# Steering_Wheel_ECU.net
KiCad netlist of a schematic drawn in Altium Designer
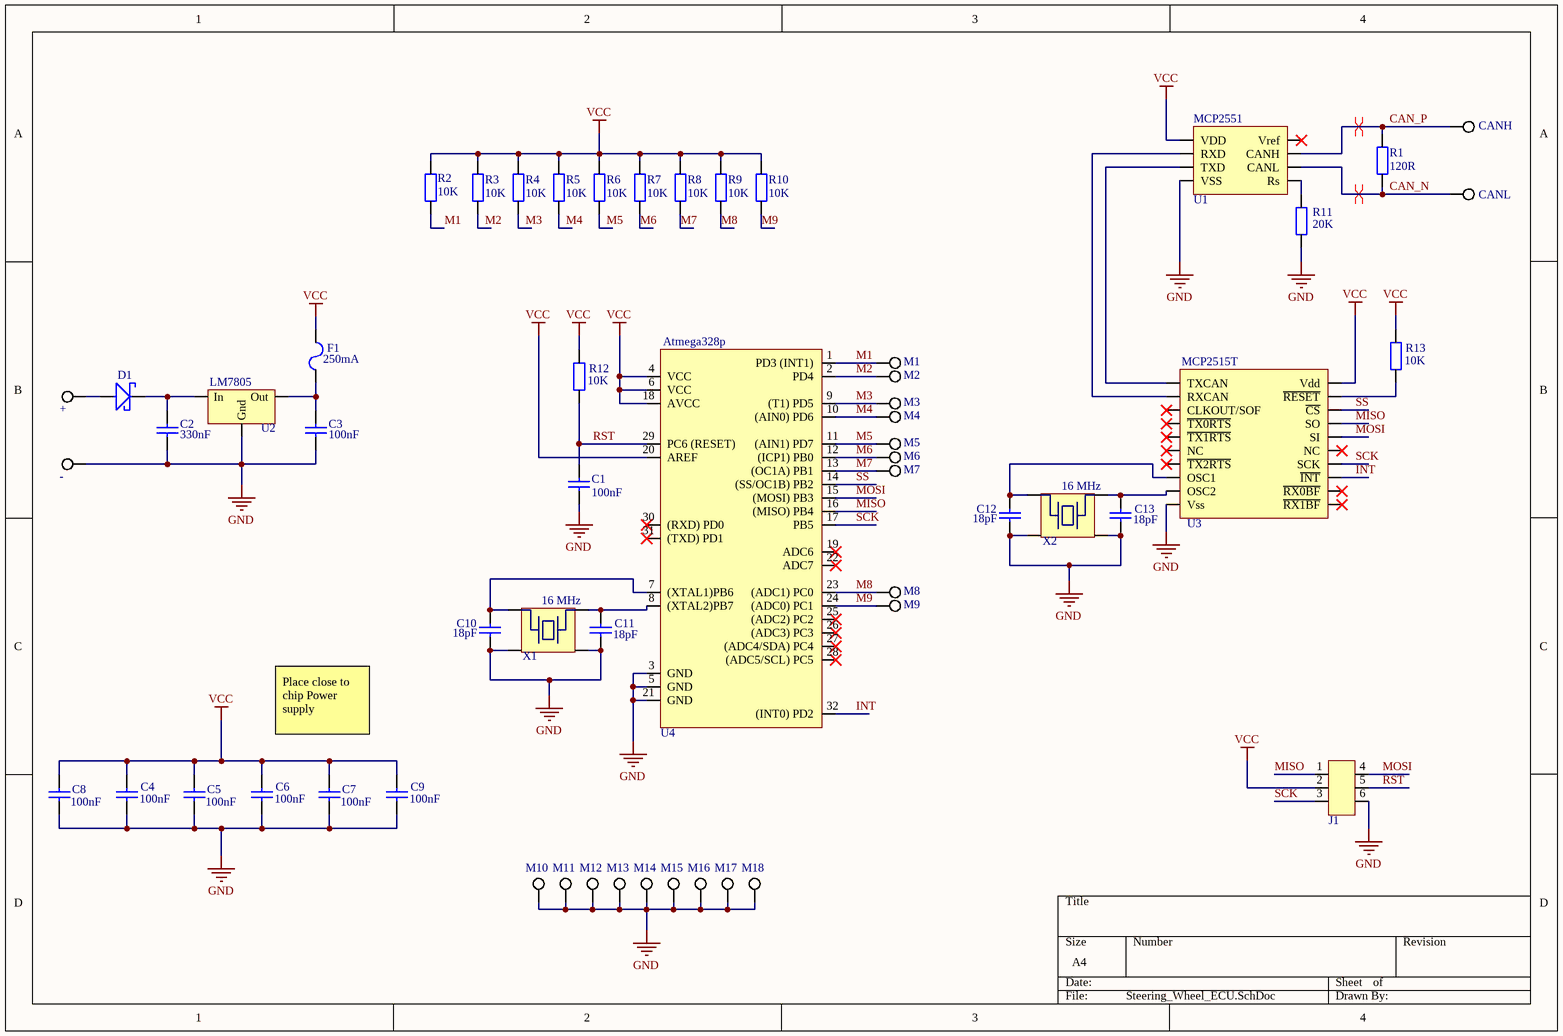
[diagram p0: Steering_Wheel_ECU.SchDoc]

(export (version "E")
  (design (tool "Eeschema 10.0.6"))
  (components
    (comp (ref "+")
      (value "0.7mm")
      (footprint "HOLE_0.7MM")
      (fields (field (name "PART NUMBER") "Hole_0.7mm"))
      (libsource (lib "Database_Libs1") (part "Hole"))
    )
    (comp (ref "-")
      (value "0.7mm")
      (footprint "HOLE_0.7MM")
      (fields (field (name "PART NUMBER") "Hole_0.7mm"))
      (libsource (lib "Database_Libs1") (part "Hole"))
    )
    (comp (ref "C1")
      (value "100nF")
      (footprint "CAPC160X80X87L35N")
      (fields
        (field (name "PART NUMBER") "C_0603_100nF_50V")
        (field (name "MANUFACTURER PART NUMBER") "CC0603MRY5V9BB104")
      )
      (libsource (lib "Database_Libs1") (part "Capacitor_NP"))
    )
    (comp (ref "C2")
      (value "330nF")
      (footprint "CAPC320X160X90L50N")
      (fields
        (field (name "PART NUMBER") "C_1206_330nF_50V")
        (field (name "MANUFACTURER PART NUMBER") "1206B334K500CT")
      )
      (libsource (lib "Database_Libs1") (part "Capacitor_NP"))
    )
    (comp (ref "C3")
      (value "100nF")
      (footprint "CAPC160X80X87L35N")
      (fields
        (field (name "PART NUMBER") "C_0603_100nF_50V")
        (field (name "MANUFACTURER PART NUMBER") "CC0603MRY5V9BB104")
      )
      (libsource (lib "Database_Libs1") (part "Capacitor_NP"))
    )
    (comp (ref "C4")
      (value "100nF")
      (footprint "CAPC160X80X87L35N")
      (fields
        (field (name "PART NUMBER") "C_0603_100nF_50V")
        (field (name "MANUFACTURER PART NUMBER") "CC0603MRY5V9BB104")
      )
      (libsource (lib "Database_Libs1") (part "Capacitor_NP"))
    )
    (comp (ref "C5")
      (value "100nF")
      (footprint "CAPC160X80X87L35N")
      (fields
        (field (name "PART NUMBER") "C_0603_100nF_50V")
        (field (name "MANUFACTURER PART NUMBER") "CC0603MRY5V9BB104")
      )
      (libsource (lib "Database_Libs1") (part "Capacitor_NP"))
    )
    (comp (ref "C6")
      (value "100nF")
      (footprint "CAPC160X80X87L35N")
      (fields
        (field (name "PART NUMBER") "C_0603_100nF_50V")
        (field (name "MANUFACTURER PART NUMBER") "CC0603MRY5V9BB104")
      )
      (libsource (lib "Database_Libs1") (part "Capacitor_NP"))
    )
    (comp (ref "C7")
      (value "100nF")
      (footprint "CAPC160X80X87L35N")
      (fields
        (field (name "PART NUMBER") "C_0603_100nF_50V")
        (field (name "MANUFACTURER PART NUMBER") "CC0603MRY5V9BB104")
      )
      (libsource (lib "Database_Libs1") (part "Capacitor_NP"))
    )
    (comp (ref "C8")
      (value "100nF")
      (footprint "CAPC160X80X87L35N")
      (fields
        (field (name "PART NUMBER") "C_0603_100nF_50V")
        (field (name "MANUFACTURER PART NUMBER") "CC0603MRY5V9BB104")
      )
      (libsource (lib "Database_Libs1") (part "Capacitor_NP"))
    )
    (comp (ref "C9")
      (value "100nF")
      (footprint "CAPC160X80X87L35N")
      (fields
        (field (name "PART NUMBER") "C_0603_100nF_50V")
        (field (name "MANUFACTURER PART NUMBER") "CC0603MRY5V9BB104")
      )
      (libsource (lib "Database_Libs1") (part "Capacitor_NP"))
    )
    (comp (ref "C10")
      (value "18pF")
      (footprint "CAPC152X76X91L25N")
      (fields
        (field (name "PART NUMBER") "C_0603_18pF_50V")
        (field (name "MANUFACTURER PART NUMBER") "06035U180GAT2A")
      )
      (libsource (lib "Database_Libs1") (part "Capacitor_NP"))
    )
    (comp (ref "C11")
      (value "18pF")
      (footprint "CAPC152X76X91L25N")
      (fields
        (field (name "PART NUMBER") "C_0603_18pF_50V")
        (field (name "MANUFACTURER PART NUMBER") "06035U180GAT2A")
      )
      (libsource (lib "Database_Libs1") (part "Capacitor_NP"))
    )
    (comp (ref "C12")
      (value "18pF")
      (footprint "CAPC152X76X91L25N")
      (fields
        (field (name "PART NUMBER") "C_0603_18pF_50V")
        (field (name "MANUFACTURER PART NUMBER") "06035U180GAT2A")
      )
      (libsource (lib "Database_Libs1") (part "Capacitor_NP"))
    )
    (comp (ref "C13")
      (value "18pF")
      (footprint "CAPC152X76X91L25N")
      (fields
        (field (name "PART NUMBER") "C_0603_18pF_50V")
        (field (name "MANUFACTURER PART NUMBER") "06035U180GAT2A")
      )
      (libsource (lib "Database_Libs1") (part "Capacitor_NP"))
    )
    (comp (ref "CANH")
      (value "0.7mm")
      (footprint "HOLE_0.7MM")
      (fields (field (name "PART NUMBER") "Hole_0.7mm"))
      (libsource (lib "Database_Libs1") (part "Hole"))
    )
    (comp (ref "CANL")
      (value "0.7mm")
      (footprint "HOLE_0.7MM")
      (fields (field (name "PART NUMBER") "Hole_0.7mm"))
      (libsource (lib "Database_Libs1") (part "Hole"))
    )
    (comp (ref "D1")
      (value "MBR0540")
      (footprint "SOD375X160X128L31X60N")
      (libsource (lib "Database_Libs1") (part "S_Diode"))
    )
    (comp (ref "F1")
      (value "250mA")
      (footprint "FUSC325X165X75L42N")
      (fields (field (name "PART NUMBER") "F_250mA") (field (name "MANUFACTURER PART NUMBER") "0ZCJ0025FF2E"))
      (libsource (lib "Database_Libs1") (part "Fuse"))
    )
    (comp (ref "J1")
      (value "Header_2x3")
      (footprint "HDRV6W64P254_3X2_762X508H1100N")
      (fields (field (name "MANUFACTURER PART NUMBER") "M20-9970345"))
      (libsource (lib "Database_Libs1") (part "Header_2x3"))
    )
    (comp (ref "M1")
      (value "0.7mm")
      (footprint "HOLE_0.7MM")
      (fields (field (name "PART NUMBER") "Hole_0.7mm"))
      (libsource (lib "Database_Libs1") (part "Hole"))
    )
    (comp (ref "M2")
      (value "0.7mm")
      (footprint "HOLE_0.7MM")
      (fields (field (name "PART NUMBER") "Hole_0.7mm"))
      (libsource (lib "Database_Libs1") (part "Hole"))
    )
    (comp (ref "M3")
      (value "0.7mm")
      (footprint "HOLE_0.7MM")
      (fields (field (name "PART NUMBER") "Hole_0.7mm"))
      (libsource (lib "Database_Libs1") (part "Hole"))
    )
    (comp (ref "M4")
      (value "0.7mm")
      (footprint "HOLE_0.7MM")
      (fields (field (name "PART NUMBER") "Hole_0.7mm"))
      (libsource (lib "Database_Libs1") (part "Hole"))
    )
    (comp (ref "M5")
      (value "0.7mm")
      (footprint "HOLE_0.7MM")
      (fields (field (name "PART NUMBER") "Hole_0.7mm"))
      (libsource (lib "Database_Libs1") (part "Hole"))
    )
    (comp (ref "M6")
      (value "0.7mm")
      (footprint "HOLE_0.7MM")
      (fields (field (name "PART NUMBER") "Hole_0.7mm"))
      (libsource (lib "Database_Libs1") (part "Hole"))
    )
    (comp (ref "M7")
      (value "0.7mm")
      (footprint "HOLE_0.7MM")
      (fields (field (name "PART NUMBER") "Hole_0.7mm"))
      (libsource (lib "Database_Libs1") (part "Hole"))
    )
    (comp (ref "M8")
      (value "0.7mm")
      (footprint "HOLE_0.7MM")
      (fields (field (name "PART NUMBER") "Hole_0.7mm"))
      (libsource (lib "Database_Libs1") (part "Hole"))
    )
    (comp (ref "M9")
      (value "0.7mm")
      (footprint "HOLE_0.7MM")
      (fields (field (name "PART NUMBER") "Hole_0.7mm"))
      (libsource (lib "Database_Libs1") (part "Hole"))
    )
    (comp (ref "M10")
      (value "0.7mm")
      (footprint "HOLE_0.7MM")
      (fields (field (name "PART NUMBER") "Hole_0.7mm"))
      (libsource (lib "Database_Libs1") (part "Hole"))
    )
    (comp (ref "M11")
      (value "0.7mm")
      (footprint "HOLE_0.7MM")
      (fields (field (name "PART NUMBER") "Hole_0.7mm"))
      (libsource (lib "Database_Libs1") (part "Hole"))
    )
    (comp (ref "M12")
      (value "0.7mm")
      (footprint "HOLE_0.7MM")
      (fields (field (name "PART NUMBER") "Hole_0.7mm"))
      (libsource (lib "Database_Libs1") (part "Hole"))
    )
    (comp (ref "M13")
      (value "0.7mm")
      (footprint "HOLE_0.7MM")
      (fields (field (name "PART NUMBER") "Hole_0.7mm"))
      (libsource (lib "Database_Libs1") (part "Hole"))
    )
    (comp (ref "M14")
      (value "0.7mm")
      (footprint "HOLE_0.7MM")
      (fields (field (name "PART NUMBER") "Hole_0.7mm"))
      (libsource (lib "Database_Libs1") (part "Hole"))
    )
    (comp (ref "M15")
      (value "0.7mm")
      (footprint "HOLE_0.7MM")
      (fields (field (name "PART NUMBER") "Hole_0.7mm"))
      (libsource (lib "Database_Libs1") (part "Hole"))
    )
    (comp (ref "M16")
      (value "0.7mm")
      (footprint "HOLE_0.7MM")
      (fields (field (name "PART NUMBER") "Hole_0.7mm"))
      (libsource (lib "Database_Libs1") (part "Hole"))
    )
    (comp (ref "M17")
      (value "0.7mm")
      (footprint "HOLE_0.7MM")
      (fields (field (name "PART NUMBER") "Hole_0.7mm"))
      (libsource (lib "Database_Libs1") (part "Hole"))
    )
    (comp (ref "M18")
      (value "0.7mm")
      (footprint "HOLE_0.7MM")
      (fields (field (name "PART NUMBER") "Hole_0.7mm"))
      (libsource (lib "Database_Libs1") (part "Hole"))
    )
    (comp (ref "R1")
      (value "120R")
      (footprint "RESC160X80X50L30N")
      (fields
        (field (name "PART NUMBER") "R_0805_120R_0W5")
        (field (name "MANUFACTURER PART NUMBER") "SG73G2ATTD1200D")
      )
      (libsource (lib "Database_Libs1") (part "Resistor"))
    )
    (comp (ref "R2")
      (value "10K")
      (footprint "RESC160X80X50L30N")
      (fields
        (field (name "PART NUMBER") "R_0603_10K_0W062_P")
        (field (name "MANUFACTURER PART NUMBER") "APC0603B10K0N")
      )
      (libsource (lib "Database_Libs1") (part "Resistor"))
    )
    (comp (ref "R3")
      (value "10K")
      (footprint "RESC160X80X50L30N")
      (fields
        (field (name "PART NUMBER") "R_0603_10K_0W062_P")
        (field (name "MANUFACTURER PART NUMBER") "APC0603B10K0N")
      )
      (libsource (lib "Database_Libs1") (part "Resistor"))
    )
    (comp (ref "R4")
      (value "10K")
      (footprint "RESC160X80X50L30N")
      (fields
        (field (name "PART NUMBER") "R_0603_10K_0W062_P")
        (field (name "MANUFACTURER PART NUMBER") "APC0603B10K0N")
      )
      (libsource (lib "Database_Libs1") (part "Resistor"))
    )
    (comp (ref "R5")
      (value "10K")
      (footprint "RESC160X80X50L30N")
      (fields
        (field (name "PART NUMBER") "R_0603_10K_0W062_P")
        (field (name "MANUFACTURER PART NUMBER") "APC0603B10K0N")
      )
      (libsource (lib "Database_Libs1") (part "Resistor"))
    )
    (comp (ref "R6")
      (value "10K")
      (footprint "RESC160X80X50L30N")
      (fields
        (field (name "PART NUMBER") "R_0603_10K_0W062_P")
        (field (name "MANUFACTURER PART NUMBER") "APC0603B10K0N")
      )
      (libsource (lib "Database_Libs1") (part "Resistor"))
    )
    (comp (ref "R7")
      (value "10K")
      (footprint "RESC160X80X50L30N")
      (fields
        (field (name "PART NUMBER") "R_0603_10K_0W062_P")
        (field (name "MANUFACTURER PART NUMBER") "APC0603B10K0N")
      )
      (libsource (lib "Database_Libs1") (part "Resistor"))
    )
    (comp (ref "R8")
      (value "10K")
      (footprint "RESC160X80X50L30N")
      (fields
        (field (name "PART NUMBER") "R_0603_10K_0W062_P")
        (field (name "MANUFACTURER PART NUMBER") "APC0603B10K0N")
      )
      (libsource (lib "Database_Libs1") (part "Resistor"))
    )
    (comp (ref "R9")
      (value "10K")
      (footprint "RESC160X80X50L30N")
      (fields
        (field (name "PART NUMBER") "R_0603_10K_0W062_P")
        (field (name "MANUFACTURER PART NUMBER") "APC0603B10K0N")
      )
      (libsource (lib "Database_Libs1") (part "Resistor"))
    )
    (comp (ref "R10")
      (value "10K")
      (footprint "RESC160X80X50L30N")
      (fields
        (field (name "PART NUMBER") "R_0603_10K_0W062_P")
        (field (name "MANUFACTURER PART NUMBER") "APC0603B10K0N")
      )
      (libsource (lib "Database_Libs1") (part "Resistor"))
    )
    (comp (ref "R11")
      (value "20K")
      (footprint "RESC160X80X50L30N")
      (fields
        (field (name "PART NUMBER") "R_0603_20K_0W1")
        (field (name "MANUFACTURER PART NUMBER") "RT0603DRE0720KL")
      )
      (libsource (lib "Database_Libs1") (part "Resistor"))
    )
    (comp (ref "R12")
      (value "10K")
      (footprint "RESC160X80X50L30N")
      (fields
        (field (name "PART NUMBER") "R_0603_10K_0W062_P")
        (field (name "MANUFACTURER PART NUMBER") "APC0603B10K0N")
      )
      (libsource (lib "Database_Libs1") (part "Resistor"))
    )
    (comp (ref "R13")
      (value "10K")
      (footprint "RESC160X80X50L30N")
      (fields
        (field (name "PART NUMBER") "R_0603_10K_0W062_P")
        (field (name "MANUFACTURER PART NUMBER") "APC0603B10K0N")
      )
      (libsource (lib "Database_Libs1") (part "Resistor"))
    )
    (comp (ref "U1")
      (value "MCP2551")
      (footprint "SOIC8P127_490X600X175L83X24N")
      (fields (field (name "MANUFACTURER PART NUMBER") "MCP2551-I/SN"))
      (libsource (lib "Database_Libs1") (part "MCP2551"))
    )
    (comp (ref "U2")
      (value "LM7805")
      (footprint "SOT223-4P230_700X180L80X75N")
      (fields (field (name "PART NUMBER") "U_5V") (field (name "MANUFACTURER PART NUMBER") "UA78M05CDCYR"))
      (libsource (lib "Database_Libs1") (part "V_REG"))
    )
    (comp (ref "U3")
      (value "MCP2515T")
      (footprint "SOP20P65_650X640X120L60X24N")
      (fields
        (field (name "PART NUMBER") "MCP2515")
        (field (name "MANUFACTURER PART NUMBER") "MCP2515T-I/ST")
      )
      (libsource (lib "Database_Libs1") (part "MCP2515"))
    )
    (comp (ref "U4")
      (value "Atmega328p")
      (footprint "QFP32P80_900X900X120L60X37N")
      (fields (field (name "MANUFACTURER PART NUMBER") "ATMEGA328P-AUR"))
      (libsource (lib "Database_Libs1") (part "Atmega328p"))
    )
    (comp (ref "X1")
      (value "16 MHz")
      (footprint "OSCCC320X250X60L90X110N")
      (fields
        (field (name "PART NUMBER") "X_16MHZ_9pF")
        (field (name "MANUFACTURER PART NUMBER") "TSX-3225 16.0000MF09Z-AC3")
      )
      (libsource (lib "Database_Libs1") (part "OSC_4pin"))
    )
    (comp (ref "X2")
      (value "16 MHz")
      (footprint "OSCCC320X250X60L90X110N")
      (fields
        (field (name "PART NUMBER") "X_16MHZ_9pF")
        (field (name "MANUFACTURER PART NUMBER") "TSX-3225 16.0000MF09Z-AC3")
      )
      (libsource (lib "Database_Libs1") (part "OSC_4pin"))
    )
  )
  (nets
    (net (code "1") (name "/CAN_N") (class "Default")
      (node (ref "CANL") (pin "1") (pinfunction "11_1") (pintype "passive"))
      (node (ref "R1") (pin "2") (pinfunction "2_2") (pintype "passive"))
      (node (ref "U1") (pin "6") (pinfunction "CANL_6") (pintype "passive"))
    )
    (net (code "2") (name "/CAN_P") (class "Default")
      (node (ref "CANH") (pin "1") (pinfunction "11_1") (pintype "passive"))
      (node (ref "R1") (pin "1") (pinfunction "1_1") (pintype "passive"))
      (node (ref "U1") (pin "7") (pinfunction "CANH_7") (pintype "passive"))
    )
    (net (code "3") (name "/INT") (class "Default")
      (node (ref "U3") (pin "13") (pinfunction "~{INT}_13") (pintype "passive"))
      (node (ref "U4") (pin "32") (pinfunction "(INT0)_PD2_32") (pintype "passive"))
    )
    (net (code "4") (name "/M1") (class "Default")
      (node (ref "M1") (pin "1") (pinfunction "11_1") (pintype "passive"))
      (node (ref "R2") (pin "2") (pinfunction "2_2") (pintype "passive"))
      (node (ref "U4") (pin "1") (pinfunction "PD3_(INT1)_1") (pintype "passive"))
    )
    (net (code "5") (name "/M2") (class "Default")
      (node (ref "M2") (pin "1") (pinfunction "11_1") (pintype "passive"))
      (node (ref "R3") (pin "1") (pinfunction "1_1") (pintype "passive"))
      (node (ref "U4") (pin "2") (pinfunction "PD4_2") (pintype "passive"))
    )
    (net (code "6") (name "/M3") (class "Default")
      (node (ref "M3") (pin "1") (pinfunction "11_1") (pintype "passive"))
      (node (ref "R4") (pin "1") (pinfunction "1_1") (pintype "passive"))
      (node (ref "U4") (pin "9") (pinfunction "(T1)_PD5_9") (pintype "passive"))
    )
    (net (code "7") (name "/M4") (class "Default")
      (node (ref "M4") (pin "1") (pinfunction "11_1") (pintype "passive"))
      (node (ref "R5") (pin "1") (pinfunction "1_1") (pintype "passive"))
      (node (ref "U4") (pin "10") (pinfunction "(AIN0)_PD6_10") (pintype "passive"))
    )
    (net (code "8") (name "/M5") (class "Default")
      (node (ref "M5") (pin "1") (pinfunction "11_1") (pintype "passive"))
      (node (ref "R6") (pin "1") (pinfunction "1_1") (pintype "passive"))
      (node (ref "U4") (pin "11") (pinfunction "(AIN1)_PD7_11") (pintype "passive"))
    )
    (net (code "9") (name "/M6") (class "Default")
      (node (ref "M6") (pin "1") (pinfunction "11_1") (pintype "passive"))
      (node (ref "R7") (pin "1") (pinfunction "1_1") (pintype "passive"))
      (node (ref "U4") (pin "12") (pinfunction "(ICP1)_PB0_12") (pintype "passive"))
    )
    (net (code "10") (name "/M7") (class "Default")
      (node (ref "M7") (pin "1") (pinfunction "11_1") (pintype "passive"))
      (node (ref "R8") (pin "1") (pinfunction "1_1") (pintype "passive"))
      (node (ref "U4") (pin "13") (pinfunction "(OC1A)_PB1_13") (pintype "passive"))
    )
    (net (code "11") (name "/M8") (class "Default")
      (node (ref "M8") (pin "1") (pinfunction "11_1") (pintype "passive"))
      (node (ref "R9") (pin "1") (pinfunction "1_1") (pintype "passive"))
      (node (ref "U4") (pin "23") (pinfunction "(ADC1)_PC0_23") (pintype "passive"))
    )
    (net (code "12") (name "/M9") (class "Default")
      (node (ref "M9") (pin "1") (pinfunction "11_1") (pintype "passive"))
      (node (ref "R10") (pin "1") (pinfunction "1_1") (pintype "passive"))
      (node (ref "U4") (pin "24") (pinfunction "(ADC0)_PC1_24") (pintype "passive"))
    )
    (net (code "13") (name "/MISO") (class "Default")
      (node (ref "J1") (pin "1") (pintype "passive"))
      (node (ref "U3") (pin "17") (pinfunction "SO_17") (pintype "passive"))
      (node (ref "U4") (pin "16") (pinfunction "(MISO)_PB4_16") (pintype "passive"))
    )
    (net (code "14") (name "/MOSI") (class "Default")
      (node (ref "J1") (pin "4") (pintype "passive"))
      (node (ref "U3") (pin "16") (pinfunction "SI_16") (pintype "passive"))
      (node (ref "U4") (pin "15") (pinfunction "(MOSI)_PB3_15") (pintype "passive"))
    )
    (net (code "15") (name "/RST") (class "Default")
      (node (ref "C1") (pin "1") (pinfunction "1_1") (pintype "passive"))
      (node (ref "J1") (pin "5") (pintype "passive"))
      (node (ref "R12") (pin "1") (pinfunction "1_1") (pintype "passive"))
      (node (ref "U4") (pin "29") (pinfunction "PC6_(RESET)_29") (pintype "passive"))
    )
    (net (code "16") (name "/SCK") (class "Default")
      (node (ref "J1") (pin "3") (pintype "passive"))
      (node (ref "U3") (pin "14") (pinfunction "SCK_14") (pintype "passive"))
      (node (ref "U4") (pin "17") (pinfunction "PB5_17") (pintype "passive"))
    )
    (net (code "17") (name "/SS") (class "Default")
      (node (ref "U3") (pin "18") (pinfunction "~{CS}_18") (pintype "passive"))
      (node (ref "U4") (pin "14") (pinfunction "(SS/OC1B)_PB2_14") (pintype "passive"))
    )
    (net (code "18") (name "GND") (class "Default")
      (node (ref "-") (pin "1") (pinfunction "11_1") (pintype "passive"))
      (node (ref "C1") (pin "2") (pinfunction "2_2") (pintype "passive"))
      (node (ref "C10") (pin "2") (pinfunction "2_2") (pintype "passive"))
      (node (ref "C11") (pin "2") (pinfunction "2_2") (pintype "passive"))
      (node (ref "C12") (pin "2") (pinfunction "2_2") (pintype "passive"))
      (node (ref "C13") (pin "2") (pinfunction "2_2") (pintype "passive"))
      (node (ref "C2") (pin "1") (pinfunction "1_1") (pintype "passive"))
      (node (ref "C3") (pin "2") (pinfunction "2_2") (pintype "passive"))
      (node (ref "C4") (pin "2") (pinfunction "2_2") (pintype "passive"))
      (node (ref "C5") (pin "2") (pinfunction "2_2") (pintype "passive"))
      (node (ref "C6") (pin "2") (pinfunction "2_2") (pintype "passive"))
      (node (ref "C7") (pin "2") (pinfunction "2_2") (pintype "passive"))
      (node (ref "C8") (pin "2") (pinfunction "2_2") (pintype "passive"))
      (node (ref "C9") (pin "2") (pinfunction "2_2") (pintype "passive"))
      (node (ref "J1") (pin "6") (pintype "passive"))
      (node (ref "M10") (pin "1") (pinfunction "11_1") (pintype "passive"))
      (node (ref "M11") (pin "1") (pinfunction "11_1") (pintype "passive"))
      (node (ref "M12") (pin "1") (pinfunction "11_1") (pintype "passive"))
      (node (ref "M13") (pin "1") (pinfunction "11_1") (pintype "passive"))
      (node (ref "M14") (pin "1") (pinfunction "11_1") (pintype "passive"))
      (node (ref "M15") (pin "1") (pinfunction "11_1") (pintype "passive"))
      (node (ref "M16") (pin "1") (pinfunction "11_1") (pintype "passive"))
      (node (ref "M17") (pin "1") (pinfunction "11_1") (pintype "passive"))
      (node (ref "M18") (pin "1") (pinfunction "11_1") (pintype "passive"))
      (node (ref "R11") (pin "1") (pinfunction "1_1") (pintype "passive"))
      (node (ref "U1") (pin "2") (pinfunction "VSS_2") (pintype "passive"))
      (node (ref "U2") (pin "2") (pinfunction "Gnd_2") (pintype "passive"))
      (node (ref "U3") (pin "10") (pinfunction "Vss_10") (pintype "passive"))
      (node (ref "U4") (pin "21") (pinfunction "GND_21") (pintype "passive"))
      (node (ref "U4") (pin "3") (pinfunction "GND_3") (pintype "passive"))
      (node (ref "U4") (pin "5") (pinfunction "GND_5") (pintype "passive"))
      (node (ref "X1") (pin "2") (pinfunction "2_2") (pintype "passive"))
      (node (ref "X1") (pin "4") (pinfunction "4_4") (pintype "passive"))
      (node (ref "X2") (pin "2") (pinfunction "2_2") (pintype "passive"))
      (node (ref "X2") (pin "4") (pinfunction "4_4") (pintype "passive"))
    )
    (net (code "19") (name "Net-(+-11)") (class "Default")
      (node (ref "+") (pin "1") (pinfunction "11_1") (pintype "passive"))
      (node (ref "D1") (pin "A") (pinfunction "A_A") (pintype "passive"))
    )
    (net (code "20") (name "Net-(D1-2)") (class "Default")
      (node (ref "C2") (pin "2") (pinfunction "2_2") (pintype "passive"))
      (node (ref "D1") (pin "C") (pinfunction "2_C") (pintype "passive"))
      (node (ref "U2") (pin "1") (pinfunction "In_1") (pintype "passive"))
    )
    (net (code "21") (name "Net-(U1-RXD)") (class "Default")
      (node (ref "U1") (pin "4") (pinfunction "RXD_4") (pintype "passive"))
      (node (ref "U3") (pin "2") (pinfunction "RXCAN_2") (pintype "passive"))
    )
    (net (code "22") (name "Net-(U1-Rs)") (class "Default")
      (node (ref "R11") (pin "2") (pinfunction "2_2") (pintype "passive"))
      (node (ref "U1") (pin "8") (pinfunction "Rs_8") (pintype "passive"))
    )
    (net (code "23") (name "Net-(U1-TXD)") (class "Default")
      (node (ref "U1") (pin "1") (pinfunction "TXD_1") (pintype "passive"))
      (node (ref "U3") (pin "1") (pinfunction "TXCAN_1") (pintype "passive"))
    )
    (net (code "24") (name "Net-(U2-Out)") (class "Default")
      (node (ref "C3") (pin "1") (pinfunction "1_1") (pintype "passive"))
      (node (ref "F1") (pin "2") (pinfunction "2_2") (pintype "passive"))
      (node (ref "U2") (pin "3") (pinfunction "Out_3") (pintype "passive"))
    )
    (net (code "25") (name "Net-(U3-OSC1)") (class "Default")
      (node (ref "C12") (pin "1") (pinfunction "1_1") (pintype "passive"))
      (node (ref "U3") (pin "9") (pinfunction "OSC1_9") (pintype "passive"))
      (node (ref "X2") (pin "3") (pinfunction "3_3") (pintype "passive"))
    )
    (net (code "26") (name "Net-(U3-OSC2)") (class "Default")
      (node (ref "C13") (pin "1") (pinfunction "1_1") (pintype "passive"))
      (node (ref "U3") (pin "8") (pinfunction "OSC2_8") (pintype "passive"))
      (node (ref "X2") (pin "1") (pinfunction "1_1") (pintype "passive"))
    )
    (net (code "27") (name "Net-(U3-~{RESET})") (class "Default")
      (node (ref "R13") (pin "1") (pinfunction "1_1") (pintype "passive"))
      (node (ref "U3") (pin "19") (pinfunction "~{RESET}_19") (pintype "passive"))
    )
    (net (code "28") (name "Net-(U4-(XTAL1)PB6)") (class "Default")
      (node (ref "C10") (pin "1") (pinfunction "1_1") (pintype "passive"))
      (node (ref "U4") (pin "7") (pinfunction "(XTAL1)PB6_7") (pintype "passive"))
      (node (ref "X1") (pin "3") (pinfunction "3_3") (pintype "passive"))
    )
    (net (code "29") (name "Net-(U4-(XTAL2)PB7)") (class "Default")
      (node (ref "C11") (pin "1") (pinfunction "1_1") (pintype "passive"))
      (node (ref "U4") (pin "8") (pinfunction "(XTAL2)PB7_8") (pintype "passive"))
      (node (ref "X1") (pin "1") (pinfunction "1_1") (pintype "passive"))
    )
    (net (code "30") (name "VCC") (class "Default")
      (node (ref "C4") (pin "1") (pinfunction "1_1") (pintype "passive"))
      (node (ref "C5") (pin "1") (pinfunction "1_1") (pintype "passive"))
      (node (ref "C6") (pin "1") (pinfunction "1_1") (pintype "passive"))
      (node (ref "C7") (pin "1") (pinfunction "1_1") (pintype "passive"))
      (node (ref "C8") (pin "1") (pinfunction "1_1") (pintype "passive"))
      (node (ref "C9") (pin "1") (pinfunction "1_1") (pintype "passive"))
      (node (ref "F1") (pin "1") (pinfunction "1_1") (pintype "passive"))
      (node (ref "J1") (pin "2") (pintype "passive"))
      (node (ref "R10") (pin "2") (pinfunction "2_2") (pintype "passive"))
      (node (ref "R12") (pin "2") (pinfunction "2_2") (pintype "passive"))
      (node (ref "R13") (pin "2") (pinfunction "2_2") (pintype "passive"))
      (node (ref "R2") (pin "1") (pinfunction "1_1") (pintype "passive"))
      (node (ref "R3") (pin "2") (pinfunction "2_2") (pintype "passive"))
      (node (ref "R4") (pin "2") (pinfunction "2_2") (pintype "passive"))
      (node (ref "R5") (pin "2") (pinfunction "2_2") (pintype "passive"))
      (node (ref "R6") (pin "2") (pinfunction "2_2") (pintype "passive"))
      (node (ref "R7") (pin "2") (pinfunction "2_2") (pintype "passive"))
      (node (ref "R8") (pin "2") (pinfunction "2_2") (pintype "passive"))
      (node (ref "R9") (pin "2") (pinfunction "2_2") (pintype "passive"))
      (node (ref "U1") (pin "3") (pinfunction "VDD_3") (pintype "passive"))
      (node (ref "U3") (pin "20") (pinfunction "Vdd_20") (pintype "passive"))
      (node (ref "U4") (pin "18") (pinfunction "AVCC_18") (pintype "passive"))
      (node (ref "U4") (pin "20") (pinfunction "AREF_20") (pintype "passive"))
      (node (ref "U4") (pin "4") (pinfunction "VCC_4") (pintype "passive"))
      (node (ref "U4") (pin "6") (pinfunction "VCC_6") (pintype "passive"))
    )
    (net (code "31") (name "unconnected-(U1-Vref-Pad5)") (class "Default")
      (node (ref "U1") (pin "5") (pinfunction "Vref_5") (pintype "passive+no_connect"))
    )
    (net (code "32") (name "unconnected-(U3-CLKOUT{slash}SOF-Pad3)") (class "Default")
      (node (ref "U3") (pin "3") (pinfunction "CLKOUT/SOF_3") (pintype "passive+no_connect"))
    )
    (net (code "33") (name "unconnected-(U3-NC-Pad6)") (class "Default")
      (node (ref "U3") (pin "6") (pinfunction "NC_6") (pintype "passive+no_connect"))
    )
    (net (code "34") (name "unconnected-(U3-NC-Pad15)") (class "Default")
      (node (ref "U3") (pin "15") (pinfunction "NC_15") (pintype "passive+no_connect"))
    )
    (net (code "35") (name "unconnected-(U3-~{RX0BF}-Pad12)") (class "Default")
      (node (ref "U3") (pin "12") (pinfunction "~{RX0BF}_12") (pintype "passive+no_connect"))
    )
    (net (code "36") (name "unconnected-(U3-~{RX1BF}-Pad11)") (class "Default")
      (node (ref "U3") (pin "11") (pinfunction "~{RX1BF}_11") (pintype "passive+no_connect"))
    )
    (net (code "37") (name "unconnected-(U3-~{TX0RTS}-Pad4)") (class "Default")
      (node (ref "U3") (pin "4") (pinfunction "~{TX0RTS}_4") (pintype "passive+no_connect"))
    )
    (net (code "38") (name "unconnected-(U3-~{TX1RTS}-Pad5)") (class "Default")
      (node (ref "U3") (pin "5") (pinfunction "~{TX1RTS}_5") (pintype "passive+no_connect"))
    )
    (net (code "39") (name "unconnected-(U3-~{TX2RTS}-Pad7)") (class "Default")
      (node (ref "U3") (pin "7") (pinfunction "~{TX2RTS}_7") (pintype "passive+no_connect"))
    )
    (net (code "40") (name "unconnected-(U4-(ADC2)_PC2-Pad25)") (class "Default")
      (node (ref "U4") (pin "25") (pinfunction "(ADC2)_PC2_25") (pintype "passive+no_connect"))
    )
    (net (code "41") (name "unconnected-(U4-(ADC3)_PC3-Pad26)") (class "Default")
      (node (ref "U4") (pin "26") (pinfunction "(ADC3)_PC3_26") (pintype "passive+no_connect"))
    )
    (net (code "42") (name "unconnected-(U4-(ADC4{slash}SDA)_PC4-Pad27)") (class "Default")
      (node (ref "U4") (pin "27") (pinfunction "(ADC4/SDA)_PC4_27") (pintype "passive+no_connect"))
    )
    (net (code "43") (name "unconnected-(U4-(ADC5{slash}SCL)_PC5-Pad28)") (class "Default")
      (node (ref "U4") (pin "28") (pinfunction "(ADC5/SCL)_PC5_28") (pintype "passive+no_connect"))
    )
    (net (code "44") (name "unconnected-(U4-(RXD)_PD0-Pad30)") (class "Default")
      (node (ref "U4") (pin "30") (pinfunction "(RXD)_PD0_30") (pintype "passive+no_connect"))
    )
    (net (code "45") (name "unconnected-(U4-(TXD)_PD1-Pad31)") (class "Default")
      (node (ref "U4") (pin "31") (pinfunction "(TXD)_PD1_31") (pintype "passive+no_connect"))
    )
    (net (code "46") (name "unconnected-(U4-ADC6-Pad19)") (class "Default")
      (node (ref "U4") (pin "19") (pinfunction "ADC6_19") (pintype "passive+no_connect"))
    )
    (net (code "47") (name "unconnected-(U4-ADC7-Pad22)") (class "Default")
      (node (ref "U4") (pin "22") (pinfunction "ADC7_22") (pintype "passive+no_connect"))
    )
  )
)
